# DualMotorBoard.net
KiCad netlist of a schematic drawn in EAGLE
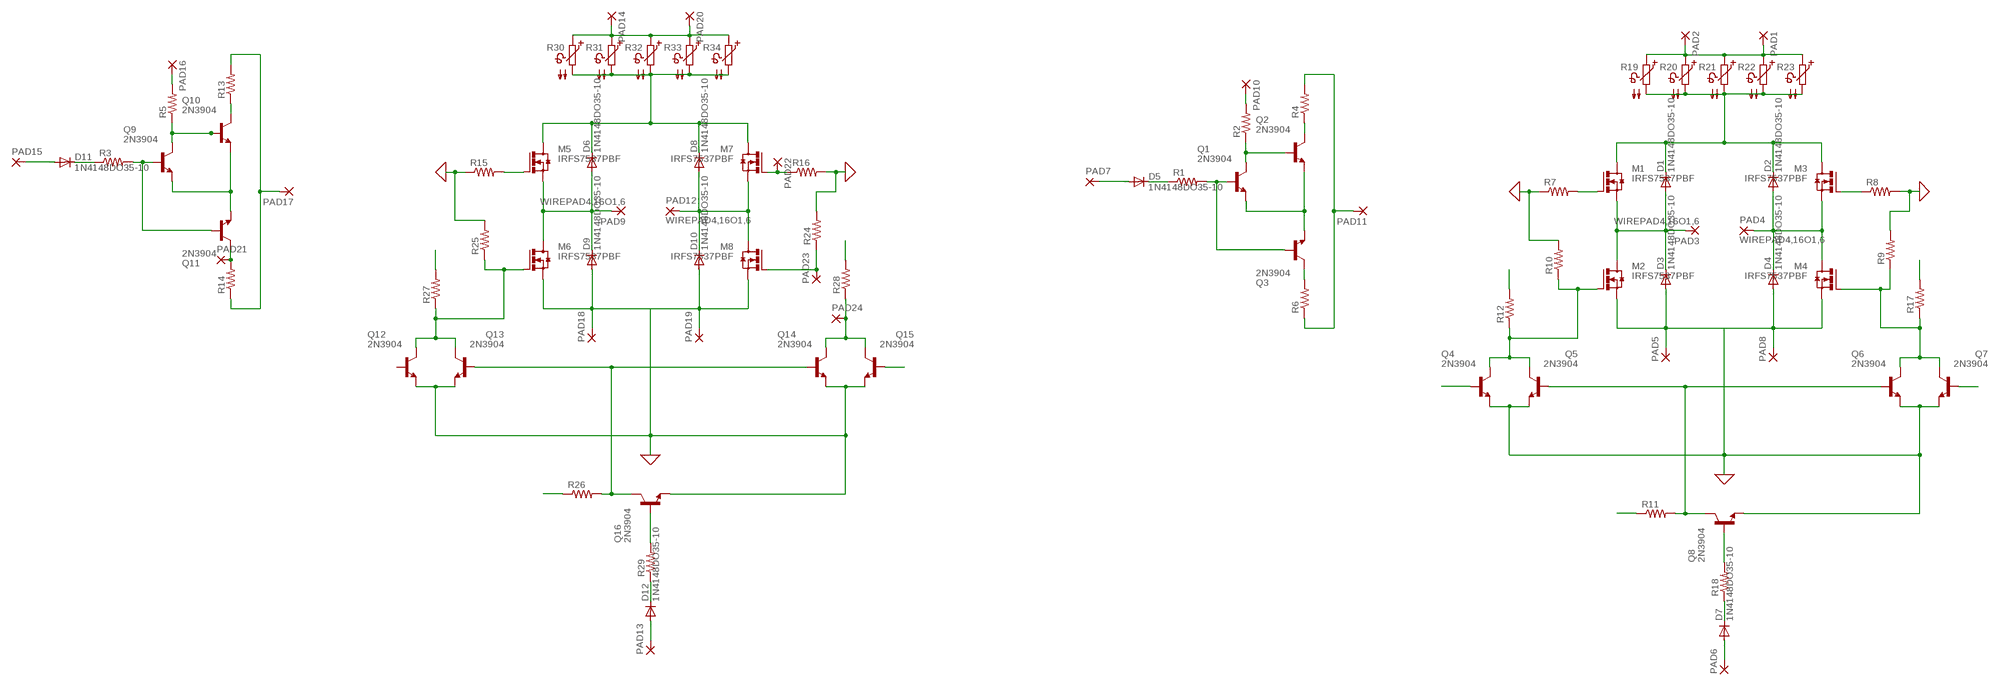
[diagram p0: schematic, sheet 1]

(export (version "E")
  (design (tool "Eeschema 10.0.6"))
  (components
    (comp (ref "D1")
      (value "1N4148DO35-10")
      (footprint "eagle-import:DO35-10")
      (libsource (lib "eagle-import") (part "1N4148DO35-10"))
    )
    (comp (ref "D2")
      (value "1N4148DO35-10")
      (footprint "eagle-import:DO35-10")
      (libsource (lib "eagle-import") (part "1N4148DO35-10"))
    )
    (comp (ref "D3")
      (value "1N4148DO35-10")
      (footprint "eagle-import:DO35-10")
      (libsource (lib "eagle-import") (part "1N4148DO35-10"))
    )
    (comp (ref "D4")
      (value "1N4148DO35-10")
      (footprint "eagle-import:DO35-10")
      (libsource (lib "eagle-import") (part "1N4148DO35-10"))
    )
    (comp (ref "D5")
      (value "1N4148DO35-10")
      (footprint "eagle-import:DO35-10")
      (libsource (lib "eagle-import") (part "1N4148DO35-10"))
    )
    (comp (ref "D6")
      (value "1N4148DO35-10")
      (footprint "eagle-import:DO35-10")
      (libsource (lib "eagle-import") (part "1N4148DO35-10"))
    )
    (comp (ref "D7")
      (value "1N4148DO35-10")
      (footprint "eagle-import:DO35-10")
      (libsource (lib "eagle-import") (part "1N4148DO35-10"))
    )
    (comp (ref "D8")
      (value "1N4148DO35-10")
      (footprint "eagle-import:DO35-10")
      (libsource (lib "eagle-import") (part "1N4148DO35-10"))
    )
    (comp (ref "D9")
      (value "1N4148DO35-10")
      (footprint "eagle-import:DO35-10")
      (libsource (lib "eagle-import") (part "1N4148DO35-10"))
    )
    (comp (ref "D10")
      (value "1N4148DO35-10")
      (footprint "eagle-import:DO35-10")
      (libsource (lib "eagle-import") (part "1N4148DO35-10"))
    )
    (comp (ref "D11")
      (value "1N4148DO35-10")
      (footprint "eagle-import:DO35-10")
      (libsource (lib "eagle-import") (part "1N4148DO35-10"))
    )
    (comp (ref "D12")
      (value "1N4148DO35-10")
      (footprint "eagle-import:DO35-10")
      (libsource (lib "eagle-import") (part "1N4148DO35-10"))
    )
    (comp (ref "M1")
      (value "IRFS7537PBF")
      (footprint "eagle-import:D2PACK")
      (libsource (lib "eagle-import") (part "IRFS7537PBF"))
    )
    (comp (ref "M2")
      (value "IRFS7537PBF")
      (footprint "eagle-import:D2PACK")
      (libsource (lib "eagle-import") (part "IRFS7537PBF"))
    )
    (comp (ref "M3")
      (value "IRFS7537PBF")
      (footprint "eagle-import:D2PACK")
      (libsource (lib "eagle-import") (part "IRFS7537PBF"))
    )
    (comp (ref "M4")
      (value "IRFS7537PBF")
      (footprint "eagle-import:D2PACK")
      (libsource (lib "eagle-import") (part "IRFS7537PBF"))
    )
    (comp (ref "M5")
      (value "IRFS7537PBF")
      (footprint "eagle-import:D2PACK")
      (libsource (lib "eagle-import") (part "IRFS7537PBF"))
    )
    (comp (ref "M6")
      (value "IRFS7537PBF")
      (footprint "eagle-import:D2PACK")
      (libsource (lib "eagle-import") (part "IRFS7537PBF"))
    )
    (comp (ref "M7")
      (value "IRFS7537PBF")
      (footprint "eagle-import:D2PACK")
      (libsource (lib "eagle-import") (part "IRFS7537PBF"))
    )
    (comp (ref "M8")
      (value "IRFS7537PBF")
      (footprint "eagle-import:D2PACK")
      (libsource (lib "eagle-import") (part "IRFS7537PBF"))
    )
    (comp (ref "PAD1")
      (value "3,81/1,4")
      (footprint "eagle-import:3,81_1,4")
      (libsource (lib "eagle-import") (part "3,81/1,4"))
    )
    (comp (ref "PAD2")
      (value "3,81/1,4")
      (footprint "eagle-import:3,81_1,4")
      (libsource (lib "eagle-import") (part "3,81/1,4"))
    )
    (comp (ref "PAD3")
      (value "WIREPAD4,16O1,6")
      (footprint "eagle-import:4,16O1,6")
      (libsource (lib "eagle-import") (part "WIREPAD4,16O1,6"))
    )
    (comp (ref "PAD4")
      (value "WIREPAD4,16O1,6")
      (footprint "eagle-import:4,16O1,6")
      (libsource (lib "eagle-import") (part "WIREPAD4,16O1,6"))
    )
    (comp (ref "PAD5")
      (value "3,81/1,4")
      (footprint "eagle-import:3,81_1,4")
      (libsource (lib "eagle-import") (part "3,81/1,4"))
    )
    (comp (ref "PAD6")
      (value "2,54/1,1")
      (footprint "eagle-import:2,54_1,1")
      (libsource (lib "eagle-import") (part "2,54/1,1"))
    )
    (comp (ref "PAD7")
      (value "2,54/1,0")
      (footprint "eagle-import:2,54_1,0")
      (libsource (lib "eagle-import") (part "2,54/1,0"))
    )
    (comp (ref "PAD8")
      (value "3,81/1,4")
      (footprint "eagle-import:3,81_1,4")
      (libsource (lib "eagle-import") (part "3,81/1,4"))
    )
    (comp (ref "PAD9")
      (value "WIREPAD4,16O1,6")
      (footprint "eagle-import:4,16O1,6")
      (libsource (lib "eagle-import") (part "WIREPAD4,16O1,6"))
    )
    (comp (ref "PAD10")
      (value "2,54/1,1")
      (footprint "eagle-import:2,54_1,1")
      (libsource (lib "eagle-import") (part "2,54/1,1"))
    )
    (comp (ref "PAD11")
      (value "2,54/1,1")
      (footprint "eagle-import:2,54_1,1")
      (libsource (lib "eagle-import") (part "2,54/1,1"))
    )
    (comp (ref "PAD12")
      (value "WIREPAD4,16O1,6")
      (footprint "eagle-import:4,16O1,6")
      (libsource (lib "eagle-import") (part "WIREPAD4,16O1,6"))
    )
    (comp (ref "PAD13")
      (value "2,54/1,1")
      (footprint "eagle-import:2,54_1,1")
      (libsource (lib "eagle-import") (part "2,54/1,1"))
    )
    (comp (ref "PAD14")
      (value "3,81/1,4")
      (footprint "eagle-import:3,81_1,4")
      (libsource (lib "eagle-import") (part "3,81/1,4"))
    )
    (comp (ref "PAD15")
      (value "2,54/1,0")
      (footprint "eagle-import:2,54_1,0")
      (libsource (lib "eagle-import") (part "2,54/1,0"))
    )
    (comp (ref "PAD16")
      (value "2,54/1,1")
      (footprint "eagle-import:2,54_1,1")
      (libsource (lib "eagle-import") (part "2,54/1,1"))
    )
    (comp (ref "PAD17")
      (value "2,54/1,1")
      (footprint "eagle-import:2,54_1,1")
      (libsource (lib "eagle-import") (part "2,54/1,1"))
    )
    (comp (ref "PAD18")
      (value "3,81/1,4")
      (footprint "eagle-import:3,81_1,4")
      (libsource (lib "eagle-import") (part "3,81/1,4"))
    )
    (comp (ref "PAD19")
      (value "3,81/1,4")
      (footprint "eagle-import:3,81_1,4")
      (libsource (lib "eagle-import") (part "3,81/1,4"))
    )
    (comp (ref "PAD20")
      (value "3,81/1,4")
      (footprint "eagle-import:3,81_1,4")
      (libsource (lib "eagle-import") (part "3,81/1,4"))
    )
    (comp (ref "PAD21")
      (value "2,54/1,1")
      (footprint "eagle-import:2,54_1,1")
      (libsource (lib "eagle-import") (part "2,54/1,1"))
    )
    (comp (ref "PAD22")
      (value "2,54/1,1")
      (footprint "eagle-import:2,54_1,1")
      (libsource (lib "eagle-import") (part "2,54/1,1"))
    )
    (comp (ref "PAD23")
      (value "2,54/1,1")
      (footprint "eagle-import:2,54_1,1")
      (libsource (lib "eagle-import") (part "2,54/1,1"))
    )
    (comp (ref "PAD24")
      (value "2,54/1,1")
      (footprint "eagle-import:2,54_1,1")
      (libsource (lib "eagle-import") (part "2,54/1,1"))
    )
    (comp (ref "Q1")
      (value "2N3904")
      (footprint "eagle-import:TO92")
      (libsource (lib "eagle-import") (part "2N3904"))
    )
    (comp (ref "Q2")
      (value "2N3904")
      (footprint "eagle-import:TO92")
      (libsource (lib "eagle-import") (part "2N3904"))
    )
    (comp (ref "Q3")
      (value "2N3904")
      (footprint "eagle-import:TO92")
      (libsource (lib "eagle-import") (part "2N3904"))
    )
    (comp (ref "Q4")
      (value "2N3904")
      (footprint "eagle-import:TO92")
      (libsource (lib "eagle-import") (part "2N3904"))
    )
    (comp (ref "Q5")
      (value "2N3904")
      (footprint "eagle-import:TO92")
      (libsource (lib "eagle-import") (part "2N3904"))
    )
    (comp (ref "Q6")
      (value "2N3904")
      (footprint "eagle-import:TO92")
      (libsource (lib "eagle-import") (part "2N3904"))
    )
    (comp (ref "Q7")
      (value "2N3904")
      (footprint "eagle-import:TO92")
      (libsource (lib "eagle-import") (part "2N3904"))
    )
    (comp (ref "Q8")
      (value "2N3904")
      (footprint "eagle-import:TO92")
      (libsource (lib "eagle-import") (part "2N3904"))
    )
    (comp (ref "Q9")
      (value "2N3904")
      (footprint "eagle-import:TO92")
      (libsource (lib "eagle-import") (part "2N3904"))
    )
    (comp (ref "Q10")
      (value "2N3904")
      (footprint "eagle-import:TO92")
      (libsource (lib "eagle-import") (part "2N3904"))
    )
    (comp (ref "Q11")
      (value "2N3904")
      (footprint "eagle-import:TO92")
      (libsource (lib "eagle-import") (part "2N3904"))
    )
    (comp (ref "Q12")
      (value "2N3904")
      (footprint "eagle-import:TO92")
      (libsource (lib "eagle-import") (part "2N3904"))
    )
    (comp (ref "Q13")
      (value "2N3904")
      (footprint "eagle-import:TO92")
      (libsource (lib "eagle-import") (part "2N3904"))
    )
    (comp (ref "Q14")
      (value "2N3904")
      (footprint "eagle-import:TO92")
      (libsource (lib "eagle-import") (part "2N3904"))
    )
    (comp (ref "Q15")
      (value "2N3904")
      (footprint "eagle-import:TO92")
      (libsource (lib "eagle-import") (part "2N3904"))
    )
    (comp (ref "Q16")
      (value "2N3904")
      (footprint "eagle-import:TO92")
      (libsource (lib "eagle-import") (part "2N3904"))
    )
    (comp (ref "R1")
      (value "R-US_0207/7")
      (footprint "eagle-import:0207_7")
      (libsource (lib "eagle-import") (part "R-US_0207/7"))
    )
    (comp (ref "R2")
      (value "R-US_0207/7")
      (footprint "eagle-import:0207_7")
      (libsource (lib "eagle-import") (part "R-US_0207/7"))
    )
    (comp (ref "R3")
      (value "R-US_0207/7")
      (footprint "eagle-import:0207_7")
      (libsource (lib "eagle-import") (part "R-US_0207/7"))
    )
    (comp (ref "R4")
      (value "R-US_0207/7")
      (footprint "eagle-import:0207_7")
      (libsource (lib "eagle-import") (part "R-US_0207/7"))
    )
    (comp (ref "R5")
      (value "R-US_0207/7")
      (footprint "eagle-import:0207_7")
      (libsource (lib "eagle-import") (part "R-US_0207/7"))
    )
    (comp (ref "R6")
      (value "R-US_0207/7")
      (footprint "eagle-import:0207_7")
      (libsource (lib "eagle-import") (part "R-US_0207/7"))
    )
    (comp (ref "R7")
      (value "R-US_0207/7")
      (footprint "eagle-import:0207_7")
      (libsource (lib "eagle-import") (part "R-US_0207/7"))
    )
    (comp (ref "R8")
      (value "R-US_0207/7")
      (footprint "eagle-import:0207_7")
      (libsource (lib "eagle-import") (part "R-US_0207/7"))
    )
    (comp (ref "R9")
      (value "R-US_0207/7")
      (footprint "eagle-import:0207_7")
      (libsource (lib "eagle-import") (part "R-US_0207/7"))
    )
    (comp (ref "R10")
      (value "R-US_0207/7")
      (footprint "eagle-import:0207_7")
      (libsource (lib "eagle-import") (part "R-US_0207/7"))
    )
    (comp (ref "R11")
      (value "R-US_0207/7")
      (footprint "eagle-import:0207_7")
      (libsource (lib "eagle-import") (part "R-US_0207/7"))
    )
    (comp (ref "R12")
      (value "R-US_0207/7")
      (footprint "eagle-import:0207_7")
      (libsource (lib "eagle-import") (part "R-US_0207/7"))
    )
    (comp (ref "R13")
      (value "R-US_0207/7")
      (footprint "eagle-import:0207_7")
      (libsource (lib "eagle-import") (part "R-US_0207/7"))
    )
    (comp (ref "R14")
      (value "R-US_0207/7")
      (footprint "eagle-import:0207_7")
      (libsource (lib "eagle-import") (part "resistor_348_R-US_0207/7"))
    )
    (comp (ref "R15")
      (value "R-US_0207/7")
      (footprint "eagle-import:0207_7")
      (libsource (lib "eagle-import") (part "resistor_348_R-US_0207/7"))
    )
    (comp (ref "R16")
      (value "R-US_0207/12")
      (footprint "eagle-import:0207_12")
      (libsource (lib "eagle-import") (part "resistor_348_R-US_0207/12"))
    )
    (comp (ref "R17")
      (value "R-US_0207/7")
      (footprint "eagle-import:0207_7")
      (libsource (lib "eagle-import") (part "resistor_348_R-US_0207/7"))
    )
    (comp (ref "R18")
      (value "R-US_0207/7")
      (footprint "eagle-import:0207_7")
      (libsource (lib "eagle-import") (part "R-US_0207/7"))
    )
    (comp (ref "R19")
      (value "PTC660A")
      (footprint "eagle-import:P660A")
      (libsource (lib "eagle-import") (part "PTC660A"))
    )
    (comp (ref "R20")
      (value "PTC660A")
      (footprint "eagle-import:P660A")
      (libsource (lib "eagle-import") (part "PTC660A"))
    )
    (comp (ref "R21")
      (value "PTC660A")
      (footprint "eagle-import:P660A")
      (libsource (lib "eagle-import") (part "PTC660A"))
    )
    (comp (ref "R22")
      (value "PTC660A")
      (footprint "eagle-import:P660A")
      (libsource (lib "eagle-import") (part "PTC660A"))
    )
    (comp (ref "R23")
      (value "PTC660A")
      (footprint "eagle-import:P660A")
      (libsource (lib "eagle-import") (part "PTC660A"))
    )
    (comp (ref "R24")
      (value "R-US_0207/12")
      (footprint "eagle-import:0207_12")
      (libsource (lib "eagle-import") (part "resistor_348_R-US_0207/12"))
    )
    (comp (ref "R25")
      (value "R-US_0207/7")
      (footprint "eagle-import:0207_7")
      (libsource (lib "eagle-import") (part "resistor_348_R-US_0207/7"))
    )
    (comp (ref "R26")
      (value "R-US_0207/7")
      (footprint "eagle-import:0207_7")
      (libsource (lib "eagle-import") (part "R-US_0207/7"))
    )
    (comp (ref "R27")
      (value "R-US_0207/7")
      (footprint "eagle-import:0207_7")
      (libsource (lib "eagle-import") (part "R-US_0207/7"))
    )
    (comp (ref "R28")
      (value "R-US_0207/7")
      (footprint "eagle-import:0207_7")
      (libsource (lib "eagle-import") (part "resistor_348_R-US_0207/7"))
    )
    (comp (ref "R29")
      (value "R-US_0207/7")
      (footprint "eagle-import:0207_7")
      (libsource (lib "eagle-import") (part "R-US_0207/7"))
    )
    (comp (ref "R30")
      (value "PTC660A")
      (footprint "eagle-import:P660A")
      (libsource (lib "eagle-import") (part "PTC660A"))
    )
    (comp (ref "R31")
      (value "PTC660A")
      (footprint "eagle-import:P660A")
      (libsource (lib "eagle-import") (part "PTC660A"))
    )
    (comp (ref "R32")
      (value "PTC660A")
      (footprint "eagle-import:P660A")
      (libsource (lib "eagle-import") (part "PTC660A"))
    )
    (comp (ref "R33")
      (value "PTC660A")
      (footprint "eagle-import:P660A")
      (libsource (lib "eagle-import") (part "PTC660A"))
    )
    (comp (ref "R34")
      (value "PTC660A")
      (footprint "eagle-import:P660A")
      (libsource (lib "eagle-import") (part "PTC660A"))
    )
  )
  (nets
    (net (code "1") (name "/BB") (class "Default")
      (node (ref "Q1") (pin "2") (pinfunction "B_2") (pintype "passive"))
      (node (ref "Q3") (pin "2") (pinfunction "B_2") (pintype "passive"))
      (node (ref "Q4") (pin "2") (pinfunction "B_2") (pintype "passive"))
      (node (ref "R1") (pin "2") (pinfunction "2_2") (pintype "passive"))
    )
    (net (code "2") (name "/BF") (class "Default")
      (node (ref "M3") (pin "1") (pinfunction "G_1") (pintype "passive"))
      (node (ref "Q3") (pin "1") (pinfunction "C_1") (pintype "passive"))
      (node (ref "R6") (pin "2") (pinfunction "2_2") (pintype "passive"))
      (node (ref "R8") (pin "1") (pinfunction "1_1") (pintype "passive"))
    )
    (net (code "3") (name "/FB") (class "Default")
      (node (ref "Q1") (pin "1") (pinfunction "C_1") (pintype "passive"))
      (node (ref "Q2") (pin "2") (pinfunction "B_2") (pintype "passive"))
      (node (ref "Q7") (pin "2") (pinfunction "B_2") (pintype "passive"))
      (node (ref "R2") (pin "1") (pinfunction "1_1") (pintype "passive"))
    )
    (net (code "4") (name "/FB1") (class "Default")
      (node (ref "Q10") (pin "2") (pinfunction "B_2") (pintype "passive"))
      (node (ref "Q15") (pin "2") (pinfunction "B_2") (pintype "passive"))
      (node (ref "Q9") (pin "1") (pinfunction "C_1") (pintype "passive"))
      (node (ref "R5") (pin "1") (pinfunction "1_1") (pintype "passive"))
    )
    (net (code "5") (name "/FF") (class "Default")
      (node (ref "M1") (pin "1") (pinfunction "G_1") (pintype "passive"))
      (node (ref "Q2") (pin "1") (pinfunction "C_1") (pintype "passive"))
      (node (ref "R4") (pin "1") (pinfunction "1_1") (pintype "passive"))
      (node (ref "R7") (pin "2") (pinfunction "2_2") (pintype "passive"))
    )
    (net (code "6") (name "/FF1") (class "Default")
      (node (ref "M5") (pin "1") (pinfunction "G_1") (pintype "passive"))
      (node (ref "Q10") (pin "1") (pinfunction "C_1") (pintype "passive"))
      (node (ref "R13") (pin "1") (pinfunction "1_1") (pintype "passive"))
      (node (ref "R15") (pin "2") (pinfunction "2_2") (pintype "passive"))
    )
    (net (code "7") (name "/VBAT") (class "Default")
      (node (ref "PAD1") (pin "1") (pinfunction "P_1") (pintype "passive"))
      (node (ref "PAD14") (pin "1") (pinfunction "P_1") (pintype "passive"))
      (node (ref "PAD2") (pin "1") (pinfunction "P_1") (pintype "passive"))
      (node (ref "PAD20") (pin "1") (pinfunction "P_1") (pintype "passive"))
      (node (ref "R19") (pin "1") (pinfunction "1_1") (pintype "passive"))
      (node (ref "R20") (pin "1") (pinfunction "1_1") (pintype "passive"))
      (node (ref "R21") (pin "1") (pinfunction "1_1") (pintype "passive"))
      (node (ref "R22") (pin "1") (pinfunction "1_1") (pintype "passive"))
      (node (ref "R23") (pin "1") (pinfunction "1_1") (pintype "passive"))
      (node (ref "R30") (pin "1") (pinfunction "1_1") (pintype "passive"))
      (node (ref "R31") (pin "1") (pinfunction "1_1") (pintype "passive"))
      (node (ref "R32") (pin "1") (pinfunction "1_1") (pintype "passive"))
      (node (ref "R33") (pin "1") (pinfunction "1_1") (pintype "passive"))
      (node (ref "R34") (pin "1") (pinfunction "1_1") (pintype "passive"))
    )
    (net (code "8") (name "/VG") (class "Default")
      (node (ref "PAD11") (pin "1") (pinfunction "P_1") (pintype "passive"))
      (node (ref "R12") (pin "2") (pinfunction "2_2") (pintype "passive"))
      (node (ref "R17") (pin "2") (pinfunction "2_2") (pintype "passive"))
      (node (ref "R4") (pin "2") (pinfunction "2_2") (pintype "passive"))
      (node (ref "R6") (pin "1") (pinfunction "1_1") (pintype "passive"))
    )
    (net (code "9") (name "/VG1") (class "Default")
      (node (ref "PAD17") (pin "1") (pinfunction "P_1") (pintype "passive"))
      (node (ref "R13") (pin "2") (pinfunction "2_2") (pintype "passive"))
      (node (ref "R14") (pin "1") (pinfunction "1_1") (pintype "passive"))
      (node (ref "R27") (pin "2") (pinfunction "2_2") (pintype "passive"))
      (node (ref "R28") (pin "2") (pinfunction "2_2") (pintype "passive"))
    )
    (net (code "10") (name "/VSW") (class "Default")
      (node (ref "PAD10") (pin "1") (pinfunction "P_1") (pintype "passive"))
      (node (ref "R11") (pin "1") (pinfunction "1_1") (pintype "passive"))
      (node (ref "R2") (pin "2") (pinfunction "2_2") (pintype "passive"))
    )
    (net (code "11") (name "/VSW1") (class "Default")
      (node (ref "PAD16") (pin "1") (pinfunction "P_1") (pintype "passive"))
      (node (ref "R26") (pin "1") (pinfunction "1_1") (pintype "passive"))
      (node (ref "R5") (pin "2") (pinfunction "2_2") (pintype "passive"))
    )
    (net (code "12") (name "GND") (class "Default")
      (node (ref "D10") (pin "A") (pinfunction "A_A") (pintype "passive"))
      (node (ref "D3") (pin "A") (pinfunction "A_A") (pintype "passive"))
      (node (ref "D4") (pin "A") (pinfunction "A_A") (pintype "passive"))
      (node (ref "D9") (pin "A") (pinfunction "A_A") (pintype "passive"))
      (node (ref "M2") (pin "3") (pinfunction "S_3") (pintype "passive"))
      (node (ref "M4") (pin "3") (pinfunction "S_3") (pintype "passive"))
      (node (ref "M6") (pin "3") (pinfunction "S_3") (pintype "passive"))
      (node (ref "M8") (pin "3") (pinfunction "S_3") (pintype "passive"))
      (node (ref "PAD18") (pin "1") (pinfunction "P_1") (pintype "passive"))
      (node (ref "PAD19") (pin "1") (pinfunction "P_1") (pintype "passive"))
      (node (ref "PAD5") (pin "1") (pinfunction "P_1") (pintype "passive"))
      (node (ref "PAD8") (pin "1") (pinfunction "P_1") (pintype "passive"))
      (node (ref "Q1") (pin "3") (pinfunction "E_3") (pintype "passive"))
      (node (ref "Q10") (pin "3") (pinfunction "E_3") (pintype "passive"))
      (node (ref "Q11") (pin "3") (pinfunction "E_3") (pintype "passive"))
      (node (ref "Q12") (pin "3") (pinfunction "E_3") (pintype "passive"))
      (node (ref "Q13") (pin "3") (pinfunction "E_3") (pintype "passive"))
      (node (ref "Q14") (pin "3") (pinfunction "E_3") (pintype "passive"))
      (node (ref "Q15") (pin "3") (pinfunction "E_3") (pintype "passive"))
      (node (ref "Q16") (pin "3") (pinfunction "E_3") (pintype "passive"))
      (node (ref "Q2") (pin "3") (pinfunction "E_3") (pintype "passive"))
      (node (ref "Q3") (pin "3") (pinfunction "E_3") (pintype "passive"))
      (node (ref "Q4") (pin "3") (pinfunction "E_3") (pintype "passive"))
      (node (ref "Q5") (pin "3") (pinfunction "E_3") (pintype "passive"))
      (node (ref "Q6") (pin "3") (pinfunction "E_3") (pintype "passive"))
      (node (ref "Q7") (pin "3") (pinfunction "E_3") (pintype "passive"))
      (node (ref "Q8") (pin "3") (pinfunction "E_3") (pintype "passive"))
      (node (ref "Q9") (pin "3") (pinfunction "E_3") (pintype "passive"))
      (node (ref "R10") (pin "2") (pinfunction "2_2") (pintype "passive"))
      (node (ref "R15") (pin "1") (pinfunction "1_1") (pintype "passive"))
      (node (ref "R16") (pin "2") (pinfunction "2_2") (pintype "passive"))
      (node (ref "R24") (pin "2") (pinfunction "2_2") (pintype "passive"))
      (node (ref "R25") (pin "2") (pinfunction "2_2") (pintype "passive"))
      (node (ref "R7") (pin "1") (pinfunction "1_1") (pintype "passive"))
      (node (ref "R8") (pin "2") (pinfunction "2_2") (pintype "passive"))
      (node (ref "R9") (pin "2") (pinfunction "2_2") (pintype "passive"))
    )
    (net (code "13") (name "Net-(D5-PadC)") (class "Default")
      (node (ref "D5") (pin "C") (pinfunction "C_C") (pintype "passive"))
      (node (ref "R1") (pin "1") (pinfunction "1_1") (pintype "passive"))
    )
    (net (code "14") (name "Net-(D7-PadC)") (class "Default")
      (node (ref "D7") (pin "C") (pinfunction "C_C") (pintype "passive"))
      (node (ref "R18") (pin "1") (pinfunction "1_1") (pintype "passive"))
    )
    (net (code "15") (name "Net-(D11-PadC)") (class "Default")
      (node (ref "D11") (pin "C") (pinfunction "C_C") (pintype "passive"))
      (node (ref "R3") (pin "1") (pinfunction "1_1") (pintype "passive"))
    )
    (net (code "16") (name "Net-(D12-PadC)") (class "Default")
      (node (ref "D12") (pin "C") (pinfunction "C_C") (pintype "passive"))
      (node (ref "R29") (pin "1") (pinfunction "1_1") (pintype "passive"))
    )
    (net (code "17") (name "Net-(M1-D)") (class "Default")
      (node (ref "D1") (pin "C") (pinfunction "C_C") (pintype "passive"))
      (node (ref "D2") (pin "C") (pinfunction "C_C") (pintype "passive"))
      (node (ref "M1") (pin "2") (pinfunction "D_2") (pintype "passive"))
      (node (ref "M3") (pin "2") (pinfunction "D_2") (pintype "passive"))
      (node (ref "R19") (pin "2") (pinfunction "2_2") (pintype "passive"))
      (node (ref "R20") (pin "2") (pinfunction "2_2") (pintype "passive"))
      (node (ref "R21") (pin "2") (pinfunction "2_2") (pintype "passive"))
      (node (ref "R22") (pin "2") (pinfunction "2_2") (pintype "passive"))
      (node (ref "R23") (pin "2") (pinfunction "2_2") (pintype "passive"))
    )
    (net (code "18") (name "Net-(M1-S)") (class "Default")
      (node (ref "D1") (pin "A") (pinfunction "A_A") (pintype "passive"))
      (node (ref "D3") (pin "C") (pinfunction "C_C") (pintype "passive"))
      (node (ref "M1") (pin "3") (pinfunction "S_3") (pintype "passive"))
      (node (ref "M2") (pin "2") (pinfunction "D_2") (pintype "passive"))
      (node (ref "PAD3") (pin "1") (pinfunction "P_1") (pintype "passive"))
    )
    (net (code "19") (name "Net-(M2-G)") (class "Default")
      (node (ref "M2") (pin "1") (pinfunction "G_1") (pintype "passive"))
      (node (ref "Q4") (pin "1") (pinfunction "C_1") (pintype "passive"))
      (node (ref "Q5") (pin "1") (pinfunction "C_1") (pintype "passive"))
      (node (ref "R10") (pin "1") (pinfunction "1_1") (pintype "passive"))
      (node (ref "R12") (pin "1") (pinfunction "1_1") (pintype "passive"))
    )
    (net (code "20") (name "Net-(M3-S)") (class "Default")
      (node (ref "D2") (pin "A") (pinfunction "A_A") (pintype "passive"))
      (node (ref "D4") (pin "C") (pinfunction "C_C") (pintype "passive"))
      (node (ref "M3") (pin "3") (pinfunction "S_3") (pintype "passive"))
      (node (ref "M4") (pin "2") (pinfunction "D_2") (pintype "passive"))
      (node (ref "PAD4") (pin "1") (pinfunction "P_1") (pintype "passive"))
    )
    (net (code "21") (name "Net-(M4-G)") (class "Default")
      (node (ref "M4") (pin "1") (pinfunction "G_1") (pintype "passive"))
      (node (ref "Q6") (pin "1") (pinfunction "C_1") (pintype "passive"))
      (node (ref "Q7") (pin "1") (pinfunction "C_1") (pintype "passive"))
      (node (ref "R17") (pin "1") (pinfunction "1_1") (pintype "passive"))
      (node (ref "R9") (pin "1") (pinfunction "1_1") (pintype "passive"))
    )
    (net (code "22") (name "Net-(M5-D)") (class "Default")
      (node (ref "D6") (pin "C") (pinfunction "C_C") (pintype "passive"))
      (node (ref "D8") (pin "C") (pinfunction "C_C") (pintype "passive"))
      (node (ref "M5") (pin "2") (pinfunction "D_2") (pintype "passive"))
      (node (ref "M7") (pin "2") (pinfunction "D_2") (pintype "passive"))
      (node (ref "R30") (pin "2") (pinfunction "2_2") (pintype "passive"))
      (node (ref "R31") (pin "2") (pinfunction "2_2") (pintype "passive"))
      (node (ref "R32") (pin "2") (pinfunction "2_2") (pintype "passive"))
      (node (ref "R33") (pin "2") (pinfunction "2_2") (pintype "passive"))
      (node (ref "R34") (pin "2") (pinfunction "2_2") (pintype "passive"))
    )
    (net (code "23") (name "Net-(M5-S)") (class "Default")
      (node (ref "D6") (pin "A") (pinfunction "A_A") (pintype "passive"))
      (node (ref "D9") (pin "C") (pinfunction "C_C") (pintype "passive"))
      (node (ref "M5") (pin "3") (pinfunction "S_3") (pintype "passive"))
      (node (ref "M6") (pin "2") (pinfunction "D_2") (pintype "passive"))
      (node (ref "PAD9") (pin "1") (pinfunction "P_1") (pintype "passive"))
    )
    (net (code "24") (name "Net-(M6-G)") (class "Default")
      (node (ref "M6") (pin "1") (pinfunction "G_1") (pintype "passive"))
      (node (ref "Q12") (pin "1") (pinfunction "C_1") (pintype "passive"))
      (node (ref "Q13") (pin "1") (pinfunction "C_1") (pintype "passive"))
      (node (ref "R25") (pin "1") (pinfunction "1_1") (pintype "passive"))
      (node (ref "R27") (pin "1") (pinfunction "1_1") (pintype "passive"))
    )
    (net (code "25") (name "Net-(M7-G)") (class "Default")
      (node (ref "M7") (pin "1") (pinfunction "G_1") (pintype "passive"))
      (node (ref "PAD22") (pin "1") (pinfunction "P_1") (pintype "passive"))
      (node (ref "R16") (pin "1") (pinfunction "1_1") (pintype "passive"))
    )
    (net (code "26") (name "Net-(M7-S)") (class "Default")
      (node (ref "D10") (pin "C") (pinfunction "C_C") (pintype "passive"))
      (node (ref "D8") (pin "A") (pinfunction "A_A") (pintype "passive"))
      (node (ref "M7") (pin "3") (pinfunction "S_3") (pintype "passive"))
      (node (ref "M8") (pin "2") (pinfunction "D_2") (pintype "passive"))
      (node (ref "PAD12") (pin "1") (pinfunction "P_1") (pintype "passive"))
    )
    (net (code "27") (name "Net-(M8-G)") (class "Default")
      (node (ref "M8") (pin "1") (pinfunction "G_1") (pintype "passive"))
      (node (ref "PAD23") (pin "1") (pinfunction "P_1") (pintype "passive"))
      (node (ref "R24") (pin "1") (pinfunction "1_1") (pintype "passive"))
    )
    (net (code "28") (name "Net-(PAD6-P)") (class "Default")
      (node (ref "D7") (pin "A") (pinfunction "A_A") (pintype "passive"))
      (node (ref "PAD6") (pin "1") (pinfunction "P_1") (pintype "passive"))
    )
    (net (code "29") (name "Net-(PAD7-P)") (class "Default")
      (node (ref "D5") (pin "A") (pinfunction "A_A") (pintype "passive"))
      (node (ref "PAD7") (pin "1") (pinfunction "P_1") (pintype "passive"))
    )
    (net (code "30") (name "Net-(PAD13-P)") (class "Default")
      (node (ref "D12") (pin "A") (pinfunction "A_A") (pintype "passive"))
      (node (ref "PAD13") (pin "1") (pinfunction "P_1") (pintype "passive"))
    )
    (net (code "31") (name "Net-(PAD15-P)") (class "Default")
      (node (ref "D11") (pin "A") (pinfunction "A_A") (pintype "passive"))
      (node (ref "PAD15") (pin "1") (pinfunction "P_1") (pintype "passive"))
    )
    (net (code "32") (name "Net-(PAD21-P)") (class "Default")
      (node (ref "PAD21") (pin "1") (pinfunction "P_1") (pintype "passive"))
      (node (ref "Q11") (pin "1") (pinfunction "C_1") (pintype "passive"))
      (node (ref "R14") (pin "2") (pinfunction "2_2") (pintype "passive"))
    )
    (net (code "33") (name "Net-(PAD24-P)") (class "Default")
      (node (ref "PAD24") (pin "1") (pinfunction "P_1") (pintype "passive"))
      (node (ref "Q14") (pin "1") (pinfunction "C_1") (pintype "passive"))
      (node (ref "Q15") (pin "1") (pinfunction "C_1") (pintype "passive"))
      (node (ref "R28") (pin "1") (pinfunction "1_1") (pintype "passive"))
    )
    (net (code "34") (name "Net-(Q5-B)") (class "Default")
      (node (ref "Q5") (pin "2") (pinfunction "B_2") (pintype "passive"))
      (node (ref "Q6") (pin "2") (pinfunction "B_2") (pintype "passive"))
      (node (ref "Q8") (pin "1") (pinfunction "C_1") (pintype "passive"))
      (node (ref "R11") (pin "2") (pinfunction "2_2") (pintype "passive"))
    )
    (net (code "35") (name "Net-(Q8-B)") (class "Default")
      (node (ref "Q8") (pin "2") (pinfunction "B_2") (pintype "passive"))
      (node (ref "R18") (pin "2") (pinfunction "2_2") (pintype "passive"))
    )
    (net (code "36") (name "Net-(Q11-B)") (class "Default")
      (node (ref "Q11") (pin "2") (pinfunction "B_2") (pintype "passive"))
      (node (ref "Q9") (pin "2") (pinfunction "B_2") (pintype "passive"))
      (node (ref "R3") (pin "2") (pinfunction "2_2") (pintype "passive"))
    )
    (net (code "37") (name "Net-(Q13-B)") (class "Default")
      (node (ref "Q13") (pin "2") (pinfunction "B_2") (pintype "passive"))
      (node (ref "Q14") (pin "2") (pinfunction "B_2") (pintype "passive"))
      (node (ref "Q16") (pin "1") (pinfunction "C_1") (pintype "passive"))
      (node (ref "R26") (pin "2") (pinfunction "2_2") (pintype "passive"))
    )
    (net (code "38") (name "Net-(Q16-B)") (class "Default")
      (node (ref "Q16") (pin "2") (pinfunction "B_2") (pintype "passive"))
      (node (ref "R29") (pin "2") (pinfunction "2_2") (pintype "passive"))
    )
    (net (code "39") (name "unconnected-(Q12-B-Pad2)") (class "Default")
      (node (ref "Q12") (pin "2") (pinfunction "B_2") (pintype "passive"))
    )
  )
)
